# toplevel_os.net
KiCad netlist of a schematic drawn in Altium Designer
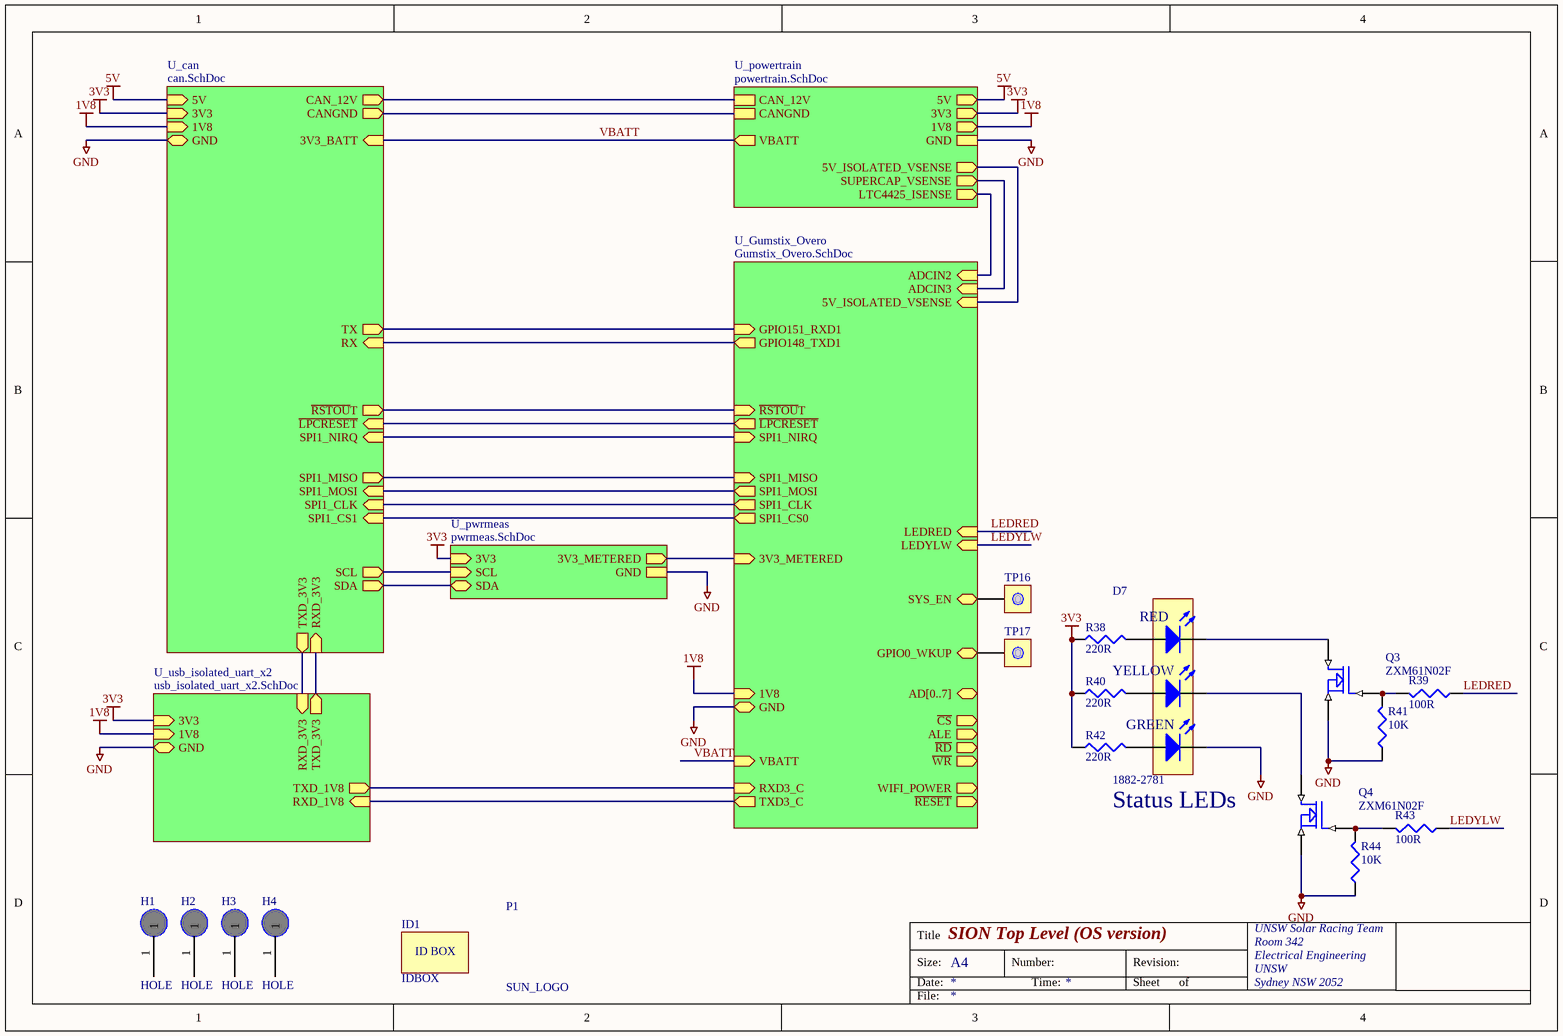
[diagram p0: toplevel_os.SchDoc]

(export (version "E")
  (design (tool "Eeschema 10.0.6"))
  (components
    (comp (ref "D7")
      (value "1882-2781")
      (footprint "LED_TRILEVEL")
      (description "Three level LED")
      (libsource (lib "RCLDQ") (part "LED-TRILEVEL"))
    )
    (comp (ref "H1")
      (value "HOLE")
      (footprint "Connectors:#6")
      (description "Hole")
      (libsource (lib "Miscellaneous") (part "HOLE"))
    )
    (comp (ref "H2")
      (value "HOLE")
      (footprint "Connectors:#6")
      (description "Hole")
      (libsource (lib "Miscellaneous") (part "HOLE"))
    )
    (comp (ref "H3")
      (value "HOLE")
      (footprint "Connectors:#6")
      (description "Hole")
      (libsource (lib "Miscellaneous") (part "HOLE"))
    )
    (comp (ref "H4")
      (value "HOLE")
      (footprint "Connectors:#6")
      (description "Hole")
      (libsource (lib "Miscellaneous") (part "HOLE"))
    )
    (comp (ref "ID1") (value "IDBOX") (footprint "IDBOX") (libsource (lib "Miscellaneous") (part "IDBOX")))
    (comp (ref "P1")
      (value "SUN_LOGO")
      (footprint "SUNSWIFTLOGO")
      (libsource (lib "Miscellaneous") (part "SUN_LOGO"))
    )
    (comp (ref "Q3")
      (value "ZXM61N02F")
      (footprint "SOT23-3")
      (description "1.7A, 20V N-Channel Enhancement mode FET")
      (libsource (lib "RCLDQ") (part "ZXM61N02F"))
    )
    (comp (ref "Q4")
      (value "ZXM61N02F")
      (footprint "SOT23-3")
      (description "1.7A, 20V N-Channel Enhancement mode FET")
      (libsource (lib "RCLDQ") (part "ZXM61N02F"))
    )
    (comp (ref "R38")
      (value "220R")
      (footprint "0603")
      (description "Resistor")
      (libsource (lib "RCLDQ") (part "RES1"))
    )
    (comp (ref "R39")
      (value "100R")
      (footprint "0603")
      (description "Resistor")
      (libsource (lib "RCLDQ") (part "RES1"))
    )
    (comp (ref "R40")
      (value "220R")
      (footprint "0603")
      (description "Resistor")
      (libsource (lib "RCLDQ") (part "RES1"))
    )
    (comp (ref "R41")
      (value "10K")
      (footprint "0603")
      (description "Resistor")
      (libsource (lib "RCLDQ") (part "RES1"))
    )
    (comp (ref "R42")
      (value "220R")
      (footprint "0603")
      (description "Resistor")
      (libsource (lib "RCLDQ") (part "RES1"))
    )
    (comp (ref "R43")
      (value "100R")
      (footprint "0603")
      (description "Resistor")
      (libsource (lib "RCLDQ") (part "RES1"))
    )
    (comp (ref "R44")
      (value "10K")
      (footprint "0603")
      (description "Resistor")
      (libsource (lib "RCLDQ") (part "RES1"))
    )
    (comp (ref "TP16")
      (value "SYS_EN")
      (footprint "TESTPOINT")
      (description "TEST POINT")
      (libsource (lib "Miscellaneous") (part "TEST"))
    )
    (comp (ref "TP17")
      (value "WKUP")
      (footprint "TESTPOINT")
      (description "TEST POINT")
      (libsource (lib "Miscellaneous") (part "TEST"))
    )
  )
  (nets
    (net (code "7") (name "/GPIO0_WKUP") (class "Default")
      (node (ref "TP17") (pin "0") (pinfunction "TP_0") (pintype "passive"))
    )
    (net (code "9") (name "/LEDRED") (class "Default")
      (node (ref "R39") (pin "1") (pinfunction "1_1") (pintype "passive"))
    )
    (net (code "10") (name "/LEDYLW") (class "Default")
      (node (ref "R43") (pin "1") (pinfunction "1_1") (pintype "passive"))
    )
    (net (code "20") (name "/SYS_EN") (class "Default")
      (node (ref "TP16") (pin "0") (pinfunction "TP_0") (pintype "passive"))
    )
    (net (code "35") (name "3V3") (class "Default")
      (node (ref "R38") (pin "1") (pinfunction "1_1") (pintype "passive"))
      (node (ref "R40") (pin "1") (pinfunction "1_1") (pintype "passive"))
      (node (ref "R42") (pin "1") (pinfunction "1_1") (pintype "passive"))
    )
    (net (code "37") (name "GND") (class "Default")
      (node (ref "D7") (pin "1") (pinfunction "K_1") (pintype "passive"))
      (node (ref "Q3") (pin "2") (pinfunction "S_2") (pintype "input"))
      (node (ref "Q4") (pin "2") (pinfunction "S_2") (pintype "input"))
      (node (ref "R41") (pin "1") (pinfunction "1_1") (pintype "passive"))
      (node (ref "R44") (pin "1") (pinfunction "1_1") (pintype "passive"))
    )
    (net (code "38") (name "Net-(D7-A-Pad4)") (class "Default")
      (node (ref "D7") (pin "4") (pinfunction "A_4") (pintype "passive"))
      (node (ref "R38") (pin "2") (pinfunction "2_2") (pintype "passive"))
    )
    (net (code "39") (name "Net-(D7-A-Pad5)") (class "Default")
      (node (ref "D7") (pin "5") (pinfunction "A_5") (pintype "passive"))
      (node (ref "R40") (pin "2") (pinfunction "2_2") (pintype "passive"))
    )
    (net (code "40") (name "Net-(D7-A-Pad6)") (class "Default")
      (node (ref "D7") (pin "6") (pinfunction "A_6") (pintype "passive"))
      (node (ref "R42") (pin "2") (pinfunction "2_2") (pintype "passive"))
    )
    (net (code "41") (name "Net-(Q3-D)") (class "Default")
      (node (ref "D7") (pin "3") (pinfunction "K_3") (pintype "passive"))
      (node (ref "Q3") (pin "3") (pinfunction "D_3") (pintype "input"))
    )
    (net (code "42") (name "Net-(Q3-G)") (class "Default")
      (node (ref "Q3") (pin "1") (pinfunction "G_1") (pintype "input"))
      (node (ref "R39") (pin "2") (pinfunction "2_2") (pintype "passive"))
      (node (ref "R41") (pin "2") (pinfunction "2_2") (pintype "passive"))
    )
    (net (code "43") (name "Net-(Q4-D)") (class "Default")
      (node (ref "D7") (pin "2") (pinfunction "K_2") (pintype "passive"))
      (node (ref "Q4") (pin "3") (pinfunction "D_3") (pintype "input"))
    )
    (net (code "44") (name "Net-(Q4-G)") (class "Default")
      (node (ref "Q4") (pin "1") (pinfunction "G_1") (pintype "input"))
      (node (ref "R43") (pin "2") (pinfunction "2_2") (pintype "passive"))
      (node (ref "R44") (pin "2") (pinfunction "2_2") (pintype "passive"))
    )
    (net (code "45") (name "unconnected-(H1-Pad1)") (class "Default")
      (node (ref "H1") (pin "1") (pinfunction "1_1") (pintype "passive"))
    )
    (net (code "46") (name "unconnected-(H2-Pad1)") (class "Default")
      (node (ref "H2") (pin "1") (pinfunction "1_1") (pintype "passive"))
    )
    (net (code "47") (name "unconnected-(H3-Pad1)") (class "Default")
      (node (ref "H3") (pin "1") (pinfunction "1_1") (pintype "passive"))
    )
    (net (code "48") (name "unconnected-(H4-Pad1)") (class "Default")
      (node (ref "H4") (pin "1") (pinfunction "1_1") (pintype "passive"))
    )
  )
)
